# esp-rs485.net
KiCad netlist of a schematic drawn in EAGLE
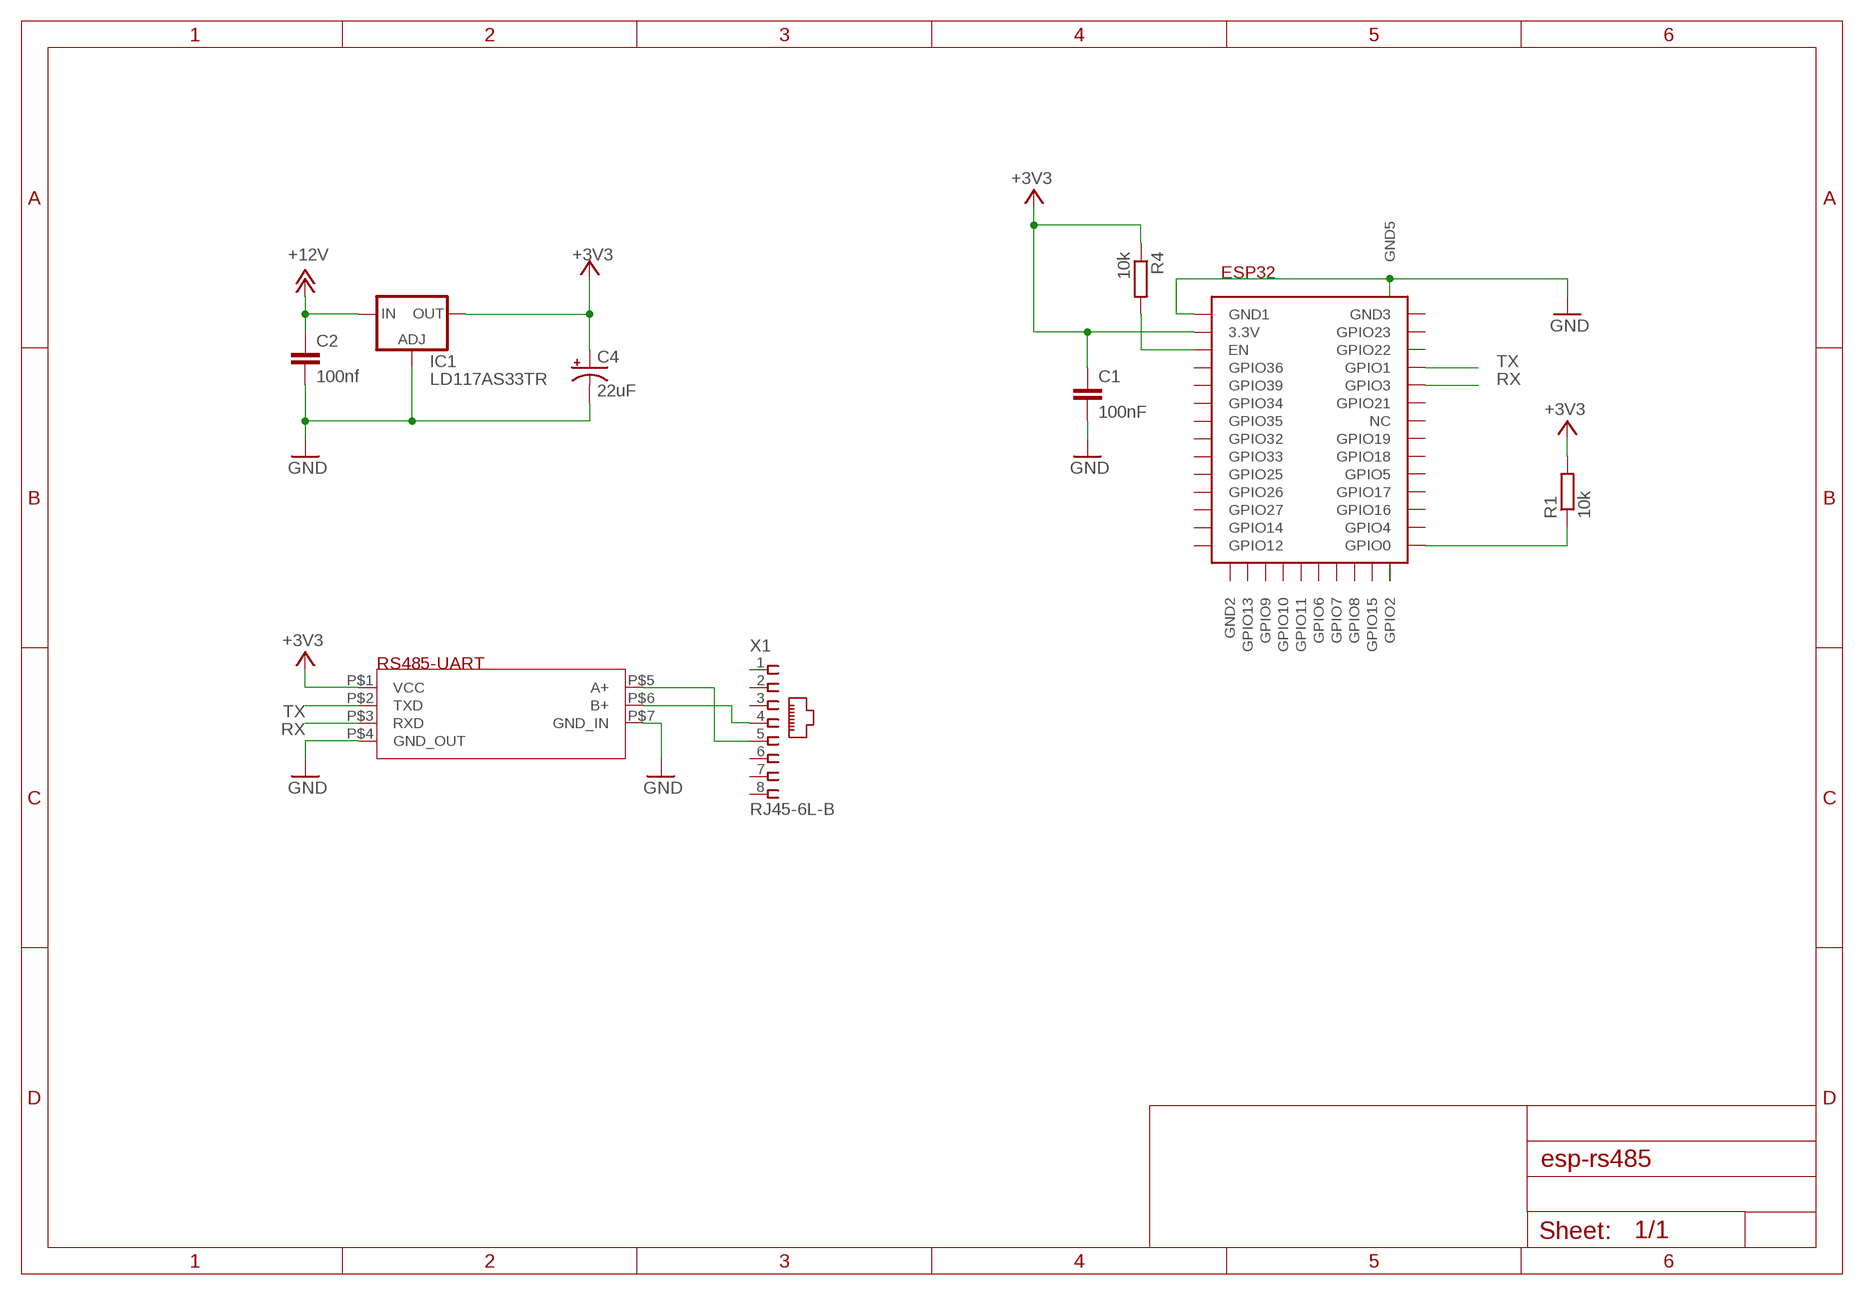
[diagram p0: schematic, sheet 1]

(export (version "E")
  (design (tool "Eeschema 10.0.6"))
  (components
    (comp (ref "C1")
      (value "100nF")
      (footprint "eagle-import:C0805K")
      (libsource (lib "eagle-import") (part "C-EUC0805K"))
    )
    (comp (ref "C2")
      (value "100nf")
      (footprint "eagle-import:C0805K")
      (libsource (lib "eagle-import") (part "C-EUC0805K"))
    )
    (comp (ref "C4")
      (value "22uF")
      (footprint "eagle-import:E2,5-5")
      (libsource (lib "eagle-import") (part "CPOL-USE2.5-5"))
    )
    (comp (ref "IC1")
      (value "LD117AS33TR")
      (footprint "eagle-import:SOT223")
      (libsource (lib "eagle-import") (part "LD117A?S33TR"))
    )
    (comp (ref "R1")
      (value "10k")
      (footprint "eagle-import:M0805")
      (libsource (lib "eagle-import") (part "R-EU_M0805"))
    )
    (comp (ref "R4")
      (value "10k")
      (footprint "eagle-import:M0805")
      (libsource (lib "eagle-import") (part "R-EU_M0805"))
    )
    (comp (ref "U$2")
      (value "ESP32-WROOM")
      (footprint "eagle-import:ESP32-WROOM")
      (libsource (lib "eagle-import") (part "ESP32-WROOM"))
    )
    (comp (ref "U$3")
      (value "RS485-ADAPTER")
      (footprint "eagle-import:RS485-ADAPTER")
      (libsource (lib "eagle-import") (part "RS485-ADAPTER"))
    )
    (comp (ref "X1")
      (value "RJ45-6L-B")
      (footprint "eagle-import:RJ45-NO-SHIELD")
      (libsource (lib "eagle-import") (part "RJ45-6L-B"))
    )
  )
  (nets
    (net (code "1") (name "+3V3") (class "Default")
      (node (ref "C1") (pin "1") (pinfunction "1_1") (pintype "passive"))
      (node (ref "C4") (pin "+") (pinfunction "+_+") (pintype "passive"))
      (node (ref "IC1") (pin "4") (pinfunction "OUT_4") (pintype "passive"))
      (node (ref "R1") (pin "2") (pinfunction "2_2") (pintype "passive"))
      (node (ref "R4") (pin "1") (pinfunction "1_1") (pintype "passive"))
      (node (ref "U$2") (pin "3V3") (pinfunction "3.3V_3V3") (pintype "bidirectional"))
      (node (ref "U$3") (pin "P$1") (pinfunction "VCC_P$1") (pintype "bidirectional"))
    )
    (net (code "2") (name "+12V") (class "Default")
      (node (ref "C2") (pin "1") (pinfunction "1_1") (pintype "passive"))
      (node (ref "IC1") (pin "3") (pinfunction "IN_3") (pintype "input"))
    )
    (net (code "3") (name "/RX") (class "Default")
      (node (ref "U$2") (pin "RX") (pinfunction "GPIO3_RX") (pintype "bidirectional"))
      (node (ref "U$3") (pin "P$3") (pinfunction "RXD_P$3") (pintype "bidirectional"))
    )
    (net (code "4") (name "/TX") (class "Default")
      (node (ref "U$2") (pin "TX") (pinfunction "GPIO1_TX") (pintype "bidirectional"))
      (node (ref "U$3") (pin "P$2") (pinfunction "TXD_P$2") (pintype "bidirectional"))
    )
    (net (code "5") (name "GND") (class "Default")
      (node (ref "C1") (pin "2") (pinfunction "2_2") (pintype "passive"))
      (node (ref "C2") (pin "2") (pinfunction "2_2") (pintype "passive"))
      (node (ref "C4") (pin "-") (pinfunction "-_-") (pintype "passive"))
      (node (ref "IC1") (pin "1") (pinfunction "ADJ_1") (pintype "input"))
      (node (ref "U$2") (pin "GND1") (pinfunction "GND1_GND1") (pintype "bidirectional"))
      (node (ref "U$2") (pin "GND5") (pinfunction "GND5_GND5") (pintype "bidirectional"))
      (node (ref "U$3") (pin "P$4") (pinfunction "GND_OUT_P$4") (pintype "bidirectional"))
      (node (ref "U$3") (pin "P$7") (pinfunction "GND_IN_P$7") (pintype "bidirectional"))
    )
    (net (code "6") (name "Net-(R4-Pad2)") (class "Default")
      (node (ref "R4") (pin "2") (pinfunction "2_2") (pintype "passive"))
      (node (ref "U$2") (pin "EN") (pinfunction "EN_EN") (pintype "bidirectional"))
    )
    (net (code "7") (name "Net-(U$2-GPIO0)") (class "Default")
      (node (ref "R1") (pin "1") (pinfunction "1_1") (pintype "passive"))
      (node (ref "U$2") (pin "IO0") (pinfunction "GPIO0_IO0") (pintype "bidirectional"))
    )
    (net (code "8") (name "Net-(U$3-A+)") (class "Default")
      (node (ref "U$3") (pin "P$5") (pinfunction "A+_P$5") (pintype "bidirectional"))
      (node (ref "X1") (pin "5") (pinfunction "5_5") (pintype "passive"))
    )
    (net (code "9") (name "Net-(U$3-B+)") (class "Default")
      (node (ref "U$3") (pin "P$6") (pinfunction "B+_P$6") (pintype "bidirectional"))
      (node (ref "X1") (pin "4") (pinfunction "4_4") (pintype "passive"))
    )
    (net (code "10") (name "unconnected-(U$2-GND2-PadGND4)") (class "Default")
      (node (ref "U$2") (pin "GND4") (pinfunction "GND2_GND4") (pintype "bidirectional"))
    )
    (net (code "11") (name "unconnected-(U$2-GND3-PadGND2)") (class "Default")
      (node (ref "U$2") (pin "GND2") (pinfunction "GND3_GND2") (pintype "bidirectional"))
    )
    (net (code "12") (name "unconnected-(U$2-GPIO2-PadIO2)") (class "Default")
      (node (ref "U$2") (pin "IO2") (pinfunction "GPIO2_IO2") (pintype "bidirectional"))
    )
    (net (code "13") (name "unconnected-(U$2-GPIO4-PadIO4)") (class "Default")
      (node (ref "U$2") (pin "IO4") (pinfunction "GPIO4_IO4") (pintype "bidirectional"))
    )
    (net (code "14") (name "unconnected-(U$2-GPIO5-PadIO5)") (class "Default")
      (node (ref "U$2") (pin "IO5") (pinfunction "GPIO5_IO5") (pintype "bidirectional"))
    )
    (net (code "15") (name "unconnected-(U$2-GPIO6-PadCLK)") (class "Default")
      (node (ref "U$2") (pin "CLK") (pinfunction "GPIO6_CLK") (pintype "bidirectional"))
    )
    (net (code "16") (name "unconnected-(U$2-GPIO7-PadSD0)") (class "Default")
      (node (ref "U$2") (pin "SD0") (pinfunction "GPIO7_SD0") (pintype "bidirectional"))
    )
    (net (code "17") (name "unconnected-(U$2-GPIO8-PadSD1)") (class "Default")
      (node (ref "U$2") (pin "SD1") (pinfunction "GPIO8_SD1") (pintype "bidirectional"))
    )
    (net (code "18") (name "unconnected-(U$2-GPIO9-PadSD2)") (class "Default")
      (node (ref "U$2") (pin "SD2") (pinfunction "GPIO9_SD2") (pintype "bidirectional"))
    )
    (net (code "19") (name "unconnected-(U$2-GPIO10-PadSD3)") (class "Default")
      (node (ref "U$2") (pin "SD3") (pinfunction "GPIO10_SD3") (pintype "bidirectional"))
    )
    (net (code "20") (name "unconnected-(U$2-GPIO11-PadCMD)") (class "Default")
      (node (ref "U$2") (pin "CMD") (pinfunction "GPIO11_CMD") (pintype "bidirectional"))
    )
    (net (code "21") (name "unconnected-(U$2-GPIO12-PadIO12)") (class "Default")
      (node (ref "U$2") (pin "IO12") (pinfunction "GPIO12_IO12") (pintype "bidirectional"))
    )
    (net (code "22") (name "unconnected-(U$2-GPIO13-PadIO13)") (class "Default")
      (node (ref "U$2") (pin "IO13") (pinfunction "GPIO13_IO13") (pintype "bidirectional"))
    )
    (net (code "23") (name "unconnected-(U$2-GPIO14-PadIO14)") (class "Default")
      (node (ref "U$2") (pin "IO14") (pinfunction "GPIO14_IO14") (pintype "bidirectional"))
    )
    (net (code "24") (name "unconnected-(U$2-GPIO15-PadIO15)") (class "Default")
      (node (ref "U$2") (pin "IO15") (pinfunction "GPIO15_IO15") (pintype "bidirectional"))
    )
    (net (code "25") (name "unconnected-(U$2-GPIO16-PadIO16)") (class "Default")
      (node (ref "U$2") (pin "IO16") (pinfunction "GPIO16_IO16") (pintype "bidirectional"))
    )
    (net (code "26") (name "unconnected-(U$2-GPIO17-PadIO17)") (class "Default")
      (node (ref "U$2") (pin "IO17") (pinfunction "GPIO17_IO17") (pintype "bidirectional"))
    )
    (net (code "27") (name "unconnected-(U$2-GPIO18-PadIO18)") (class "Default")
      (node (ref "U$2") (pin "IO18") (pinfunction "GPIO18_IO18") (pintype "bidirectional"))
    )
    (net (code "28") (name "unconnected-(U$2-GPIO19-PadIO19)") (class "Default")
      (node (ref "U$2") (pin "IO19") (pinfunction "GPIO19_IO19") (pintype "bidirectional"))
    )
    (net (code "29") (name "unconnected-(U$2-GPIO21-PadIO21)") (class "Default")
      (node (ref "U$2") (pin "IO21") (pinfunction "GPIO21_IO21") (pintype "bidirectional"))
    )
    (net (code "30") (name "unconnected-(U$2-GPIO22-PadIO22)") (class "Default")
      (node (ref "U$2") (pin "IO22") (pinfunction "GPIO22_IO22") (pintype "bidirectional"))
    )
    (net (code "31") (name "unconnected-(U$2-GPIO23-PadIO23)") (class "Default")
      (node (ref "U$2") (pin "IO23") (pinfunction "GPIO23_IO23") (pintype "bidirectional"))
    )
    (net (code "32") (name "unconnected-(U$2-GPIO25-PadIO25)") (class "Default")
      (node (ref "U$2") (pin "IO25") (pinfunction "GPIO25_IO25") (pintype "bidirectional"))
    )
    (net (code "33") (name "unconnected-(U$2-GPIO26-PadIO26)") (class "Default")
      (node (ref "U$2") (pin "IO26") (pinfunction "GPIO26_IO26") (pintype "bidirectional"))
    )
    (net (code "34") (name "unconnected-(U$2-GPIO27-PadIO27)") (class "Default")
      (node (ref "U$2") (pin "IO27") (pinfunction "GPIO27_IO27") (pintype "bidirectional"))
    )
    (net (code "35") (name "unconnected-(U$2-GPIO32-PadIO32)") (class "Default")
      (node (ref "U$2") (pin "IO32") (pinfunction "GPIO32_IO32") (pintype "bidirectional"))
    )
    (net (code "36") (name "unconnected-(U$2-GPIO33-PadIO33)") (class "Default")
      (node (ref "U$2") (pin "IO33") (pinfunction "GPIO33_IO33") (pintype "bidirectional"))
    )
    (net (code "37") (name "unconnected-(U$2-GPIO34-PadIO34)") (class "Default")
      (node (ref "U$2") (pin "IO34") (pinfunction "GPIO34_IO34") (pintype "bidirectional"))
    )
    (net (code "38") (name "unconnected-(U$2-GPIO35-PadIO35)") (class "Default")
      (node (ref "U$2") (pin "IO35") (pinfunction "GPIO35_IO35") (pintype "bidirectional"))
    )
    (net (code "39") (name "unconnected-(U$2-GPIO36-PadSENSOR_VP)") (class "Default")
      (node (ref "U$2") (pin "SENSOR_VP") (pinfunction "GPIO36_SENSOR_VP") (pintype "bidirectional"))
    )
    (net (code "40") (name "unconnected-(U$2-GPIO39-PadSENSOR_VN)") (class "Default")
      (node (ref "U$2") (pin "SENSOR_VN") (pinfunction "GPIO39_SENSOR_VN") (pintype "bidirectional"))
    )
    (net (code "41") (name "unconnected-(U$2-NC-PadGND3)") (class "Default")
      (node (ref "U$2") (pin "GND3") (pinfunction "NC_GND3") (pintype "bidirectional"))
    )
    (net (code "42") (name "unconnected-(X1-Pad1)") (class "Default")
      (node (ref "X1") (pin "1") (pinfunction "1_1") (pintype "passive"))
    )
    (net (code "43") (name "unconnected-(X1-Pad2)") (class "Default")
      (node (ref "X1") (pin "2") (pinfunction "2_2") (pintype "passive"))
    )
    (net (code "44") (name "unconnected-(X1-Pad3)") (class "Default")
      (node (ref "X1") (pin "3") (pinfunction "3_3") (pintype "passive"))
    )
    (net (code "45") (name "unconnected-(X1-Pad6)") (class "Default")
      (node (ref "X1") (pin "6") (pinfunction "6_6") (pintype "passive"))
    )
    (net (code "46") (name "unconnected-(X1-Pad7)") (class "Default")
      (node (ref "X1") (pin "7") (pinfunction "7_7") (pintype "passive"))
    )
    (net (code "47") (name "unconnected-(X1-Pad8)") (class "Default")
      (node (ref "X1") (pin "8") (pinfunction "8_8") (pintype "passive"))
    )
  )
)
